# SRF_Light_Switch.net
KiCad netlist of a schematic drawn in EAGLE
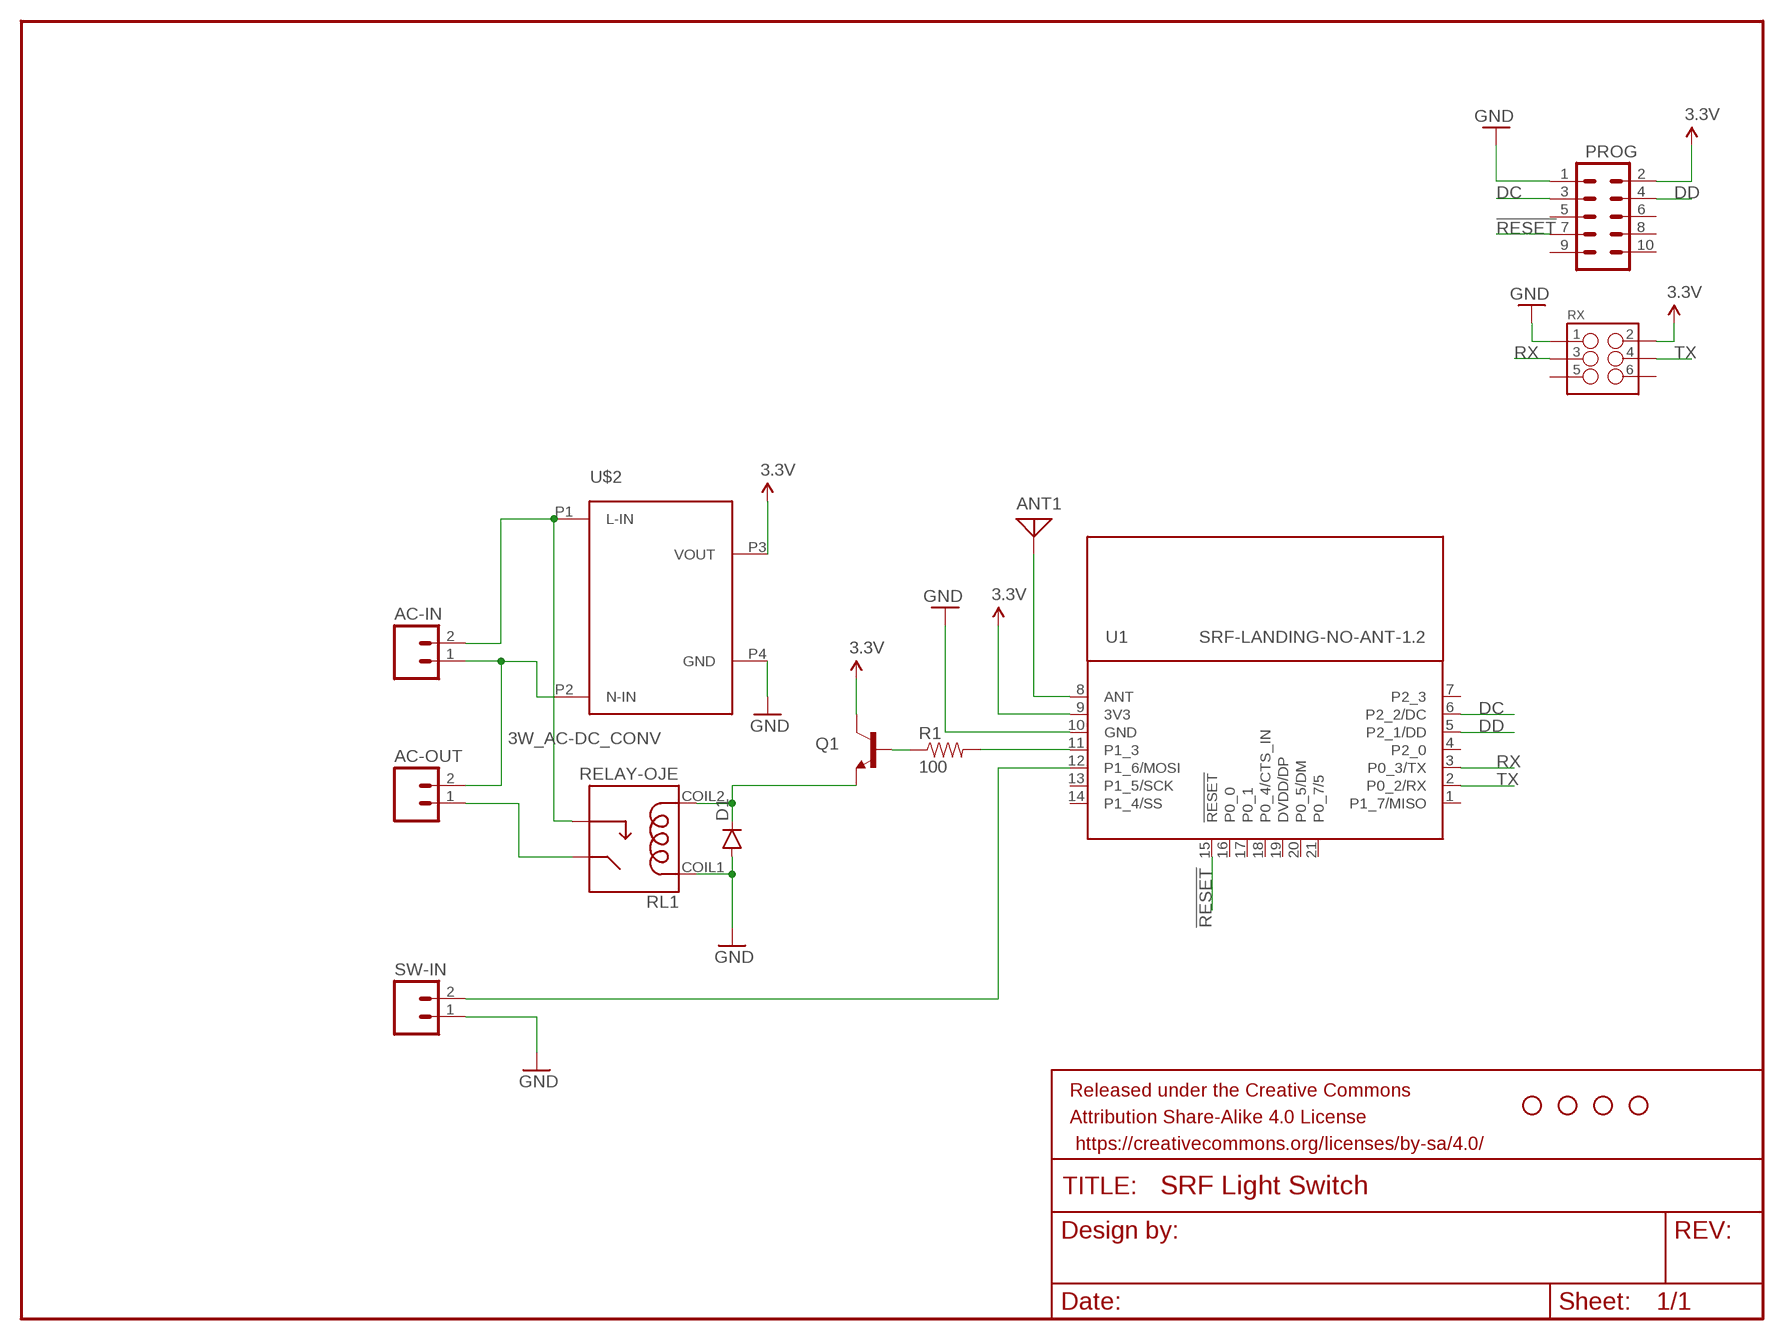
[diagram p0: schematic, sheet 1]

(export (version "E")
  (design (tool "Eeschema 10.0.6"))
  (components
    (comp (ref "AC-IN")
      (value "M025MM")
      (footprint "eagle-import:SCREWTERMINAL-5MM-2")
      (libsource (lib "eagle-import") (part "M025MM"))
    )
    (comp (ref "AC-OUT")
      (value "M025MM")
      (footprint "eagle-import:SCREWTERMINAL-5MM-2")
      (libsource (lib "eagle-import") (part "M025MM"))
    )
    (comp (ref "ANT1")
      (value "ANTENNA")
      (footprint "eagle-import:PAD-01")
      (libsource (lib "eagle-import") (part "ANTENNA"))
    )
    (comp (ref "D1")
      (value "DIODEPTH")
      (footprint "eagle-import:DIODE-1N4001")
      (libsource (lib "eagle-import") (part "DIODEPTH"))
    )
    (comp (ref "FRAME1")
      (value "FRAME-LETTER")
      (footprint "eagle-import:CREATIVE_COMMONS")
      (fields (field (name "DESIGNER") "NAME"))
      (libsource (lib "eagle-import") (part "FRAME-LETTER"))
    )
    (comp (ref "PROG")
      (value "M05X2SHD")
      (footprint "eagle-import:2X5-SHROUDED")
      (libsource (lib "eagle-import") (part "M05X2SHD"))
    )
    (comp (ref "Q1")
      (value "TRANSISTOR_NPNTO92")
      (footprint "eagle-import:TO-92")
      (libsource (lib "eagle-import") (part "TRANSISTOR_NPNTO92"))
    )
    (comp (ref "R1")
      (value "100")
      (footprint "eagle-import:AXIAL-0.4")
      (libsource (lib "eagle-import") (part "RESISTORPTH-1/4W"))
    )
    (comp (ref "RL1")
      (value "RELAY-OJE")
      (footprint "eagle-import:RELAY-OJE")
      (libsource (lib "eagle-import") (part "RELAY-OJE"))
    )
    (comp (ref "RX")
      (value "M03X2SHROUD")
      (footprint "eagle-import:2X3-SHROUDED")
      (libsource (lib "eagle-import") (part "M03X2SHROUD"))
    )
    (comp (ref "STANDOFF1")
      (value "STAND-OFF")
      (footprint "eagle-import:STAND-OFF")
      (libsource (lib "eagle-import") (part "STAND-OFF"))
    )
    (comp (ref "STANDOFF2")
      (value "STAND-OFF")
      (footprint "eagle-import:STAND-OFF")
      (libsource (lib "eagle-import") (part "STAND-OFF"))
    )
    (comp (ref "STANDOFF3")
      (value "STAND-OFF")
      (footprint "eagle-import:STAND-OFF")
      (libsource (lib "eagle-import") (part "STAND-OFF"))
    )
    (comp (ref "STANDOFF4")
      (value "STAND-OFF")
      (footprint "eagle-import:STAND-OFF")
      (libsource (lib "eagle-import") (part "STAND-OFF"))
    )
    (comp (ref "SW-IN")
      (value "M025MM")
      (footprint "eagle-import:SCREWTERMINAL-5MM-2")
      (libsource (lib "eagle-import") (part "M025MM"))
    )
    (comp (ref "U$2")
      (value "3W_AC-DC_CONV")
      (footprint "eagle-import:3W_AC-DC_CONV")
      (libsource (lib "eagle-import") (part "3W_AC-DC_CONV"))
    )
    (comp (ref "U1")
      (value "SRF-LANDING-NO-ANT-1.2")
      (footprint "eagle-import:SRF-LANDING-NO-ANT-1.2")
      (libsource (lib "eagle-import") (part "SRF-LANDING-NO-ANT-1.2"))
    )
  )
  (nets
    (net (code "1") (name "/DC") (class "Default")
      (node (ref "PROG") (pin "3") (pinfunction "3_3") (pintype "passive"))
      (node (ref "U1") (pin "6") (pinfunction "P2_2/DC_6") (pintype "bidirectional"))
    )
    (net (code "2") (name "/DD") (class "Default")
      (node (ref "PROG") (pin "4") (pinfunction "4_4") (pintype "passive"))
      (node (ref "U1") (pin "5") (pinfunction "P2_1/DD_5") (pintype "bidirectional"))
    )
    (net (code "3") (name "/RX") (class "Default")
      (node (ref "RX") (pin "3") (pinfunction "3_3") (pintype "bidirectional"))
      (node (ref "U1") (pin "3") (pinfunction "P0_3/TX_3") (pintype "bidirectional"))
    )
    (net (code "4") (name "/TX") (class "Default")
      (node (ref "RX") (pin "4") (pinfunction "4_4") (pintype "bidirectional"))
      (node (ref "U1") (pin "2") (pinfunction "P0_2/RX_2") (pintype "bidirectional"))
    )
    (net (code "5") (name "/~{RESET}") (class "Default")
      (node (ref "PROG") (pin "7") (pinfunction "7_7") (pintype "passive"))
      (node (ref "U1") (pin "15") (pinfunction "~{RESET}_15") (pintype "input"))
    )
    (net (code "6") (name "3.3V") (class "Default")
      (node (ref "PROG") (pin "2") (pinfunction "2_2") (pintype "passive"))
      (node (ref "Q1") (pin "3") (pinfunction "C_3") (pintype "passive"))
      (node (ref "RX") (pin "2") (pinfunction "2_2") (pintype "bidirectional"))
      (node (ref "U$2") (pin "P3") (pinfunction "VOUT_P3") (pintype "bidirectional"))
      (node (ref "U1") (pin "9") (pinfunction "3V3_9") (pintype "power_in"))
    )
    (net (code "7") (name "GND") (class "Default")
      (node (ref "D1") (pin "A") (pinfunction "A_A") (pintype "passive"))
      (node (ref "PROG") (pin "1") (pinfunction "1_1") (pintype "passive"))
      (node (ref "RL1") (pin "COIL1") (pinfunction "COIL1_COIL1") (pintype "bidirectional"))
      (node (ref "RX") (pin "1") (pinfunction "1_1") (pintype "bidirectional"))
      (node (ref "SW-IN") (pin "1") (pinfunction "1_1") (pintype "passive"))
      (node (ref "U$2") (pin "P4") (pinfunction "GND_P4") (pintype "bidirectional"))
      (node (ref "U1") (pin "10") (pinfunction "GND_10") (pintype "power_in"))
    )
    (net (code "8") (name "Net-(AC-OUT-Pad1)") (class "Default")
      (node (ref "AC-OUT") (pin "1") (pinfunction "1_1") (pintype "passive"))
      (node (ref "RL1") (pin "COM") (pinfunction "COM_COM") (pintype "bidirectional"))
    )
    (net (code "9") (name "Net-(Q1-B)") (class "Default")
      (node (ref "Q1") (pin "2") (pinfunction "B_2") (pintype "passive"))
      (node (ref "R1") (pin "P$1") (pinfunction "1_P$1") (pintype "passive"))
    )
    (net (code "10") (name "Net-(Q1-E)") (class "Default")
      (node (ref "D1") (pin "C") (pinfunction "C_C") (pintype "passive"))
      (node (ref "Q1") (pin "1") (pinfunction "E_1") (pintype "passive"))
      (node (ref "RL1") (pin "COIL2") (pinfunction "COIL2_COIL2") (pintype "bidirectional"))
    )
    (net (code "11") (name "Net-(R1-2)") (class "Default")
      (node (ref "R1") (pin "P$2") (pinfunction "2_P$2") (pintype "passive"))
      (node (ref "U1") (pin "11") (pinfunction "P1_3_11") (pintype "bidirectional"))
    )
    (net (code "12") (name "Net-(U$2-L-IN)") (class "Default")
      (node (ref "AC-IN") (pin "2") (pinfunction "2_2") (pintype "passive"))
      (node (ref "RL1") (pin "NO") (pinfunction "NO_NO") (pintype "bidirectional"))
      (node (ref "U$2") (pin "P1") (pinfunction "L-IN_P1") (pintype "bidirectional"))
    )
    (net (code "13") (name "Net-(U$2-N-IN)") (class "Default")
      (node (ref "AC-IN") (pin "1") (pinfunction "1_1") (pintype "passive"))
      (node (ref "AC-OUT") (pin "2") (pinfunction "2_2") (pintype "passive"))
      (node (ref "U$2") (pin "P2") (pinfunction "N-IN_P2") (pintype "bidirectional"))
    )
    (net (code "14") (name "Net-(U1-ANT)") (class "Default")
      (node (ref "ANT1") (pin "1") (pinfunction "1_1") (pintype "output"))
      (node (ref "U1") (pin "8") (pinfunction "ANT_8") (pintype "output"))
    )
    (net (code "15") (name "Net-(U1-P1_6{slash}MOSI)") (class "Default")
      (node (ref "SW-IN") (pin "2") (pinfunction "2_2") (pintype "passive"))
      (node (ref "U1") (pin "12") (pinfunction "P1_6/MOSI_12") (pintype "bidirectional"))
    )
    (net (code "16") (name "unconnected-(PROG-Pad5)") (class "Default")
      (node (ref "PROG") (pin "5") (pinfunction "5_5") (pintype "passive"))
    )
    (net (code "17") (name "unconnected-(PROG-Pad6)") (class "Default")
      (node (ref "PROG") (pin "6") (pinfunction "6_6") (pintype "passive"))
    )
    (net (code "18") (name "unconnected-(PROG-Pad8)") (class "Default")
      (node (ref "PROG") (pin "8") (pinfunction "8_8") (pintype "passive"))
    )
    (net (code "19") (name "unconnected-(PROG-Pad9)") (class "Default")
      (node (ref "PROG") (pin "9") (pinfunction "9_9") (pintype "passive"))
    )
    (net (code "20") (name "unconnected-(PROG-Pad10)") (class "Default")
      (node (ref "PROG") (pin "10") (pinfunction "10_10") (pintype "passive"))
    )
    (net (code "21") (name "unconnected-(RX-Pad5)") (class "Default")
      (node (ref "RX") (pin "5") (pinfunction "5_5") (pintype "bidirectional"))
    )
    (net (code "22") (name "unconnected-(RX-Pad6)") (class "Default")
      (node (ref "RX") (pin "6") (pinfunction "6_6") (pintype "bidirectional"))
    )
    (net (code "23") (name "unconnected-(U1-DVDD{slash}DP-Pad19)") (class "Default")
      (node (ref "U1") (pin "19") (pinfunction "DVDD/DP_19") (pintype "bidirectional"))
    )
    (net (code "24") (name "unconnected-(U1-P0_0-Pad16)") (class "Default")
      (node (ref "U1") (pin "16") (pinfunction "P0_0_16") (pintype "bidirectional"))
    )
    (net (code "25") (name "unconnected-(U1-P0_1-Pad17)") (class "Default")
      (node (ref "U1") (pin "17") (pinfunction "P0_1_17") (pintype "bidirectional"))
    )
    (net (code "26") (name "unconnected-(U1-P0_4{slash}CTS_IN-Pad18)") (class "Default")
      (node (ref "U1") (pin "18") (pinfunction "P0_4/CTS_IN_18") (pintype "bidirectional"))
    )
    (net (code "27") (name "unconnected-(U1-P0_5{slash}DM-Pad20)") (class "Default")
      (node (ref "U1") (pin "20") (pinfunction "P0_5/DM_20") (pintype "bidirectional"))
    )
    (net (code "28") (name "unconnected-(U1-P0_7{slash}5-Pad21)") (class "Default")
      (node (ref "U1") (pin "21") (pinfunction "P0_7/5_21") (pintype "bidirectional"))
    )
    (net (code "29") (name "unconnected-(U1-P1_4{slash}SS-Pad14)") (class "Default")
      (node (ref "U1") (pin "14") (pinfunction "P1_4/SS_14") (pintype "bidirectional"))
    )
    (net (code "30") (name "unconnected-(U1-P1_5{slash}SCK-Pad13)") (class "Default")
      (node (ref "U1") (pin "13") (pinfunction "P1_5/SCK_13") (pintype "bidirectional"))
    )
    (net (code "31") (name "unconnected-(U1-P1_7{slash}MISO-Pad1)") (class "Default")
      (node (ref "U1") (pin "1") (pinfunction "P1_7/MISO_1") (pintype "bidirectional"))
    )
    (net (code "32") (name "unconnected-(U1-P2_0-Pad4)") (class "Default")
      (node (ref "U1") (pin "4") (pinfunction "P2_0_4") (pintype "bidirectional"))
    )
    (net (code "33") (name "unconnected-(U1-P2_3-Pad7)") (class "Default")
      (node (ref "U1") (pin "7") (pinfunction "P2_3_7") (pintype "bidirectional"))
    )
  )
)
